# Left_Bar.net
KiCad netlist of a schematic drawn in EAGLE
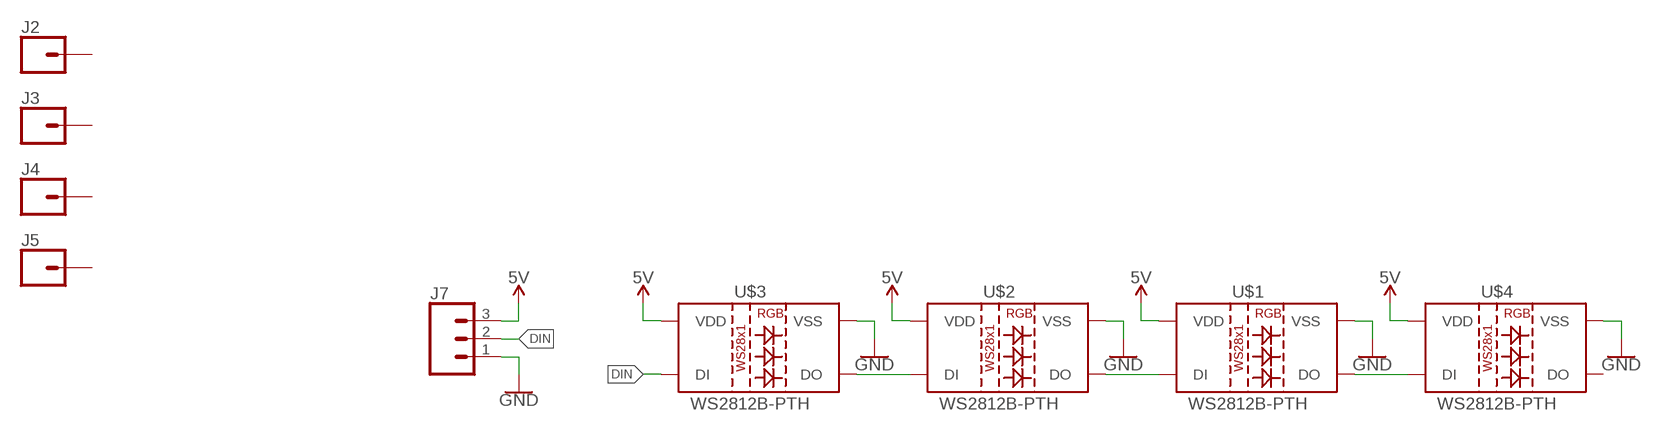
[diagram p0: schematic, sheet 1]

(export (version "E")
  (design (tool "Eeschema 10.0.6"))
  (components
    (comp (ref "J2")
      (value "CONN_01OFFSET")
      (footprint "eagle-import:1X01_OFFSET")
      (libsource (lib "eagle-import") (part "CONN_01OFFSET"))
    )
    (comp (ref "J3")
      (value "CONN_01OFFSET")
      (footprint "eagle-import:1X01_OFFSET")
      (libsource (lib "eagle-import") (part "CONN_01OFFSET"))
    )
    (comp (ref "J4")
      (value "CONN_01OFFSET")
      (footprint "eagle-import:1X01_OFFSET")
      (libsource (lib "eagle-import") (part "CONN_01OFFSET"))
    )
    (comp (ref "J5")
      (value "CONN_01OFFSET")
      (footprint "eagle-import:1X01_OFFSET")
      (libsource (lib "eagle-import") (part "CONN_01OFFSET"))
    )
    (comp (ref "J7")
      (value "CONN_03")
      (footprint "eagle-import:1X03")
      (libsource (lib "eagle-import") (part "CONN_03"))
    )
    (comp (ref "U$1")
      (value "WS2812B-PTH")
      (footprint "eagle-import:WS2812B-PTH-KIT")
      (libsource (lib "eagle-import") (part "WS2812B-PTH"))
    )
    (comp (ref "U$2")
      (value "WS2812B-PTH")
      (footprint "eagle-import:WS2812B-PTH-KIT")
      (libsource (lib "eagle-import") (part "WS2812B-PTH"))
    )
    (comp (ref "U$3")
      (value "WS2812B-PTH")
      (footprint "eagle-import:WS2812B-PTH-KIT")
      (libsource (lib "eagle-import") (part "WS2812B-PTH"))
    )
    (comp (ref "U$4")
      (value "WS2812B-PTH")
      (footprint "eagle-import:WS2812B-PTH-KIT")
      (libsource (lib "eagle-import") (part "WS2812B-PTH"))
    )
  )
  (nets
    (net (code "1") (name "5V") (class "Default")
      (node (ref "J7") (pin "3") (pinfunction "3_3") (pintype "passive"))
      (node (ref "U$1") (pin "2") (pinfunction "VDD_2") (pintype "bidirectional"))
      (node (ref "U$2") (pin "2") (pinfunction "VDD_2") (pintype "bidirectional"))
      (node (ref "U$3") (pin "2") (pinfunction "VDD_2") (pintype "bidirectional"))
      (node (ref "U$4") (pin "2") (pinfunction "VDD_2") (pintype "bidirectional"))
    )
    (net (code "2") (name "DIN") (class "Default")
      (node (ref "J7") (pin "2") (pinfunction "2_2") (pintype "passive"))
      (node (ref "U$3") (pin "1") (pinfunction "DI_1") (pintype "bidirectional"))
    )
    (net (code "3") (name "GND") (class "Default")
      (node (ref "J7") (pin "1") (pinfunction "1_1") (pintype "passive"))
      (node (ref "U$1") (pin "3") (pinfunction "VSS_3") (pintype "bidirectional"))
      (node (ref "U$2") (pin "3") (pinfunction "VSS_3") (pintype "bidirectional"))
      (node (ref "U$3") (pin "3") (pinfunction "VSS_3") (pintype "bidirectional"))
      (node (ref "U$4") (pin "3") (pinfunction "VSS_3") (pintype "bidirectional"))
    )
    (net (code "4") (name "Net-(U$1-DI)") (class "Default")
      (node (ref "U$1") (pin "1") (pinfunction "DI_1") (pintype "bidirectional"))
      (node (ref "U$2") (pin "4") (pinfunction "DO_4") (pintype "bidirectional"))
    )
    (net (code "5") (name "Net-(U$1-DO)") (class "Default")
      (node (ref "U$1") (pin "4") (pinfunction "DO_4") (pintype "bidirectional"))
      (node (ref "U$4") (pin "1") (pinfunction "DI_1") (pintype "bidirectional"))
    )
    (net (code "6") (name "Net-(U$2-DI)") (class "Default")
      (node (ref "U$2") (pin "1") (pinfunction "DI_1") (pintype "bidirectional"))
      (node (ref "U$3") (pin "4") (pinfunction "DO_4") (pintype "bidirectional"))
    )
    (net (code "7") (name "unconnected-(J2-Pad1)") (class "Default")
      (node (ref "J2") (pin "1") (pinfunction "1_1") (pintype "passive"))
    )
    (net (code "8") (name "unconnected-(J3-Pad1)") (class "Default")
      (node (ref "J3") (pin "1") (pinfunction "1_1") (pintype "passive"))
    )
    (net (code "9") (name "unconnected-(J4-Pad1)") (class "Default")
      (node (ref "J4") (pin "1") (pinfunction "1_1") (pintype "passive"))
    )
    (net (code "10") (name "unconnected-(J5-Pad1)") (class "Default")
      (node (ref "J5") (pin "1") (pinfunction "1_1") (pintype "passive"))
    )
    (net (code "11") (name "unconnected-(U$4-DO-Pad4)") (class "Default")
      (node (ref "U$4") (pin "4") (pinfunction "DO_4") (pintype "bidirectional"))
    )
  )
)
